# ADAPT_MAXREFDES117.net
KiCad netlist of a schematic drawn in EAGLE
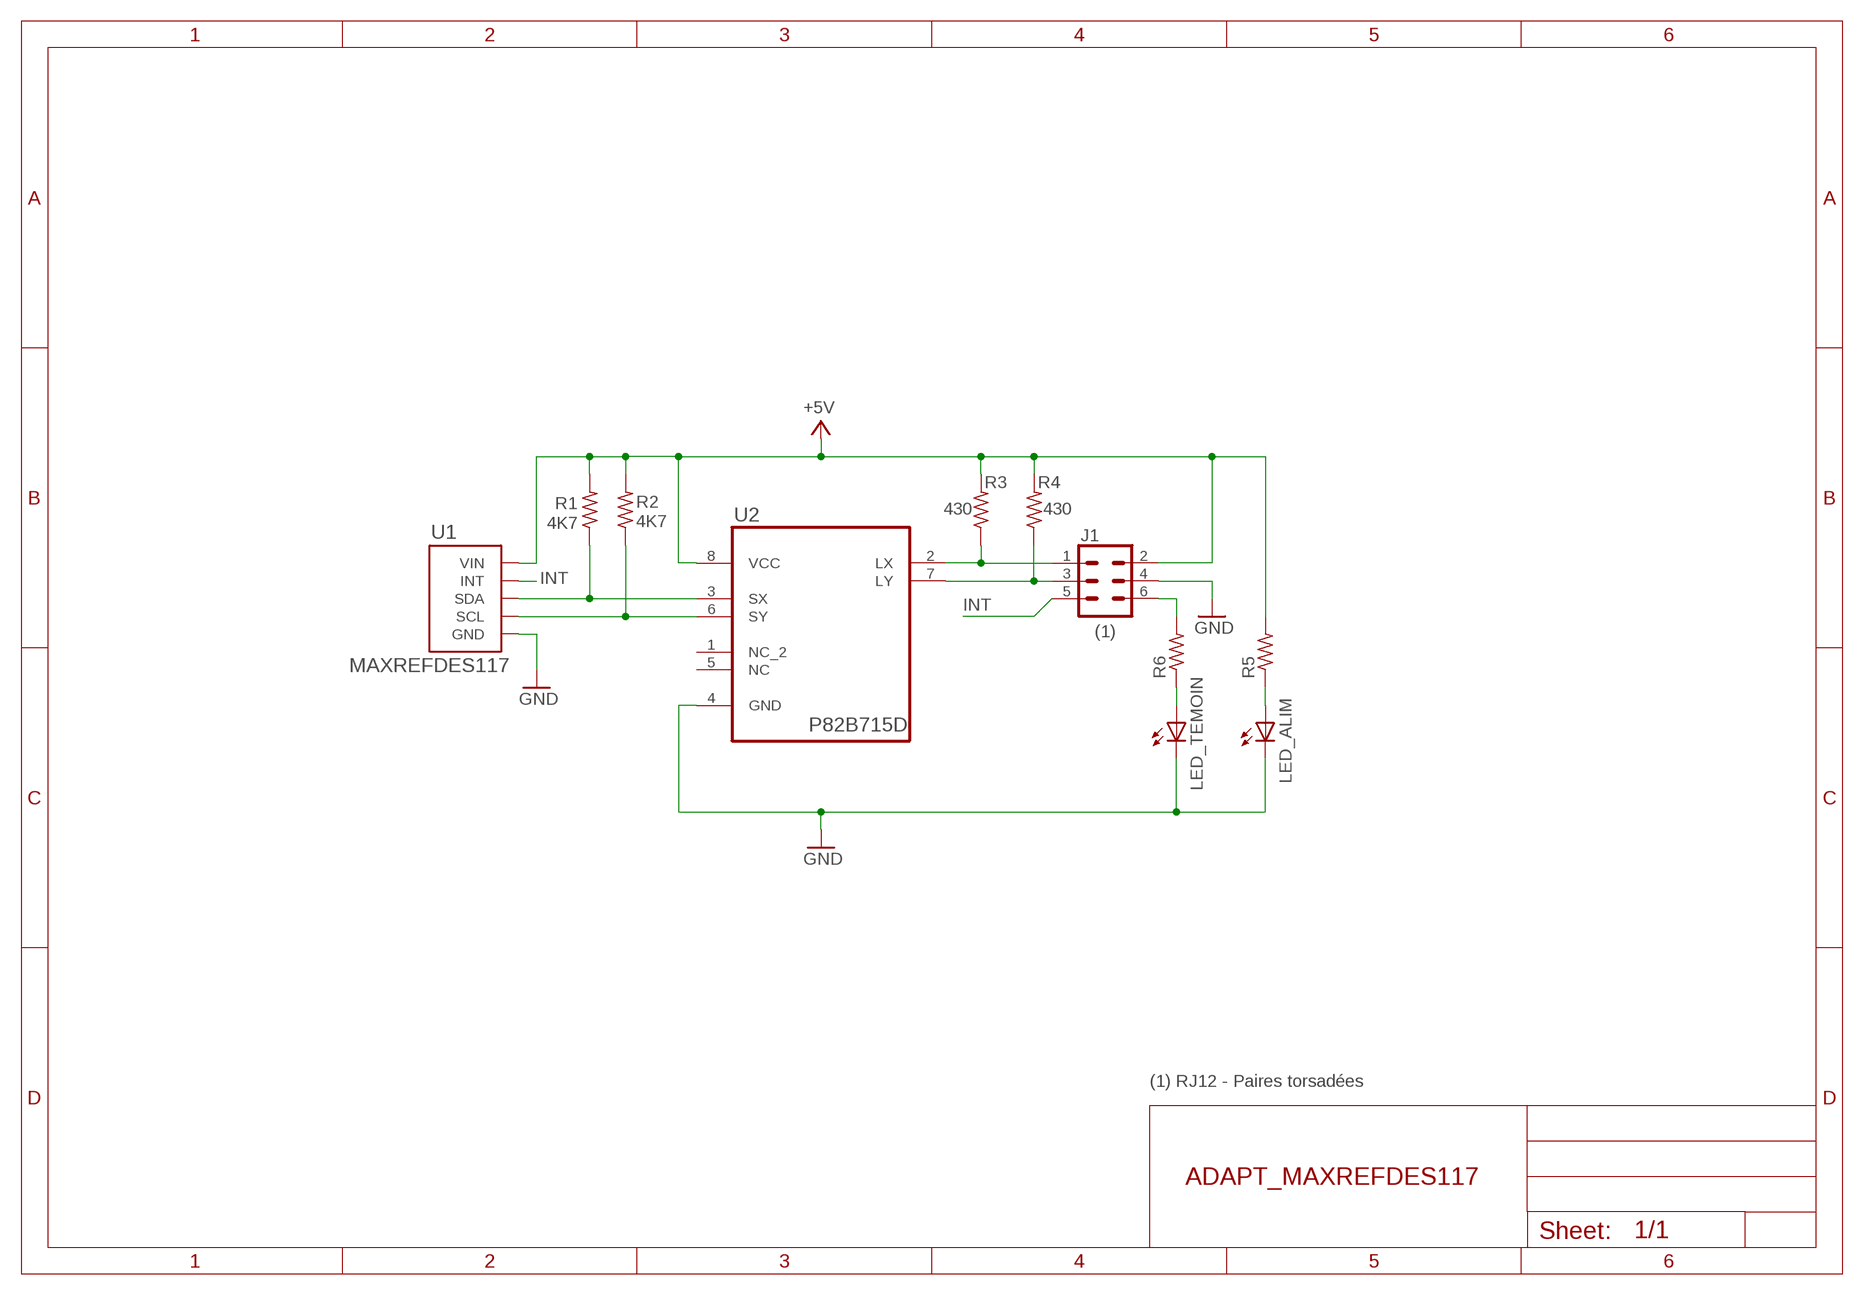
[diagram p0: schematic, sheet 1]

(export (version "E")
  (design (tool "Eeschema 10.0.6"))
  (components
    (comp (ref "J1")
      (value "CONN_03X2NO_SILK")
      (footprint "eagle-import:2X3-NS")
      (libsource (lib "eagle-import") (part "CONN_03X2NO_SILK"))
    )
    (comp (ref "LED_ALIM")
      (value "LEDFAB1206")
      (footprint "eagle-import:LED1206FAB")
      (libsource (lib "eagle-import") (part "LEDFAB1206"))
    )
    (comp (ref "LED_TEMOIN")
      (value "LEDFAB1206")
      (footprint "eagle-import:LED1206FAB")
      (libsource (lib "eagle-import") (part "LEDFAB1206"))
    )
    (comp (ref "R1")
      (value "4K7")
      (footprint "eagle-import:R1206FAB")
      (libsource (lib "eagle-import") (part "RES-US1206FAB"))
    )
    (comp (ref "R2")
      (value "4K7")
      (footprint "eagle-import:R1206FAB")
      (libsource (lib "eagle-import") (part "RES-US1206FAB"))
    )
    (comp (ref "R3")
      (value "430")
      (footprint "eagle-import:R1206FAB")
      (libsource (lib "eagle-import") (part "RES-US1206FAB"))
    )
    (comp (ref "R4")
      (value "430")
      (footprint "eagle-import:R1206FAB")
      (libsource (lib "eagle-import") (part "RES-US1206FAB"))
    )
    (comp (ref "R5")
      (value "RES-US1206FAB")
      (footprint "eagle-import:R1206FAB")
      (libsource (lib "eagle-import") (part "RES-US1206FAB"))
    )
    (comp (ref "R6")
      (value "RES-US1206FAB")
      (footprint "eagle-import:R1206FAB")
      (libsource (lib "eagle-import") (part "RES-US1206FAB"))
    )
    (comp (ref "U1")
      (value "MAXREFDES117")
      (footprint "eagle-import:MAXREFDES117")
      (libsource (lib "eagle-import") (part "MAXREFDES117"))
    )
    (comp (ref "U2")
      (value "P82B715D")
      (footprint "eagle-import:SOIC127P600X175-8N")
      (fields (field (name "MF") "Texas Instruments"))
      (libsource (lib "eagle-import") (part "P82B715D"))
    )
  )
  (nets
    (net (code "1") (name "+5V") (class "Default")
      (node (ref "J1") (pin "2") (pinfunction "2_2") (pintype "bidirectional"))
      (node (ref "R1") (pin "2") (pinfunction "2_2") (pintype "passive"))
      (node (ref "R2") (pin "2") (pinfunction "2_2") (pintype "passive"))
      (node (ref "R3") (pin "2") (pinfunction "2_2") (pintype "passive"))
      (node (ref "R4") (pin "2") (pinfunction "2_2") (pintype "passive"))
      (node (ref "R5") (pin "2") (pinfunction "2_2") (pintype "passive"))
      (node (ref "U1") (pin "VIN") (pinfunction "VIN_VIN") (pintype "bidirectional"))
      (node (ref "U2") (pin "8") (pinfunction "VCC_8") (pintype "power_in"))
    )
    (net (code "2") (name "/INT") (class "Default")
      (node (ref "J1") (pin "5") (pinfunction "5_5") (pintype "bidirectional"))
      (node (ref "U1") (pin "INT$1") (pinfunction "INT_INT$1") (pintype "bidirectional"))
      (node (ref "U1") (pin "INT$2") (pinfunction "INT_INT$2") (pintype "bidirectional"))
    )
    (net (code "3") (name "GND") (class "Default")
      (node (ref "J1") (pin "4") (pinfunction "4_4") (pintype "bidirectional"))
      (node (ref "LED_ALIM") (pin "2") (pinfunction "C_2") (pintype "passive"))
      (node (ref "LED_TEMOIN") (pin "2") (pinfunction "C_2") (pintype "passive"))
      (node (ref "U1") (pin "GND") (pinfunction "GND_GND") (pintype "bidirectional"))
      (node (ref "U2") (pin "4") (pinfunction "GND_4") (pintype "passive"))
    )
    (net (code "4") (name "Net-(J1-Pad6)") (class "Default")
      (node (ref "J1") (pin "6") (pinfunction "6_6") (pintype "bidirectional"))
      (node (ref "R6") (pin "2") (pinfunction "2_2") (pintype "passive"))
    )
    (net (code "5") (name "Net-(LED_ALIM-A)") (class "Default")
      (node (ref "LED_ALIM") (pin "1") (pinfunction "A_1") (pintype "passive"))
      (node (ref "R5") (pin "1") (pinfunction "1_1") (pintype "passive"))
    )
    (net (code "6") (name "Net-(LED_TEMOIN-A)") (class "Default")
      (node (ref "LED_TEMOIN") (pin "1") (pinfunction "A_1") (pintype "passive"))
      (node (ref "R6") (pin "1") (pinfunction "1_1") (pintype "passive"))
    )
    (net (code "7") (name "Net-(U2-LX)") (class "Default")
      (node (ref "J1") (pin "1") (pinfunction "1_1") (pintype "bidirectional"))
      (node (ref "R3") (pin "1") (pinfunction "1_1") (pintype "passive"))
      (node (ref "U2") (pin "2") (pinfunction "LX_2") (pintype "output"))
    )
    (net (code "8") (name "Net-(U2-LY)") (class "Default")
      (node (ref "J1") (pin "3") (pinfunction "3_3") (pintype "bidirectional"))
      (node (ref "R4") (pin "1") (pinfunction "1_1") (pintype "passive"))
      (node (ref "U2") (pin "7") (pinfunction "LY_7") (pintype "output"))
    )
    (net (code "9") (name "Net-(U2-SX)") (class "Default")
      (node (ref "R1") (pin "1") (pinfunction "1_1") (pintype "passive"))
      (node (ref "U1") (pin "SDA$1") (pinfunction "SDA_SDA$1") (pintype "bidirectional"))
      (node (ref "U1") (pin "SDA$2") (pinfunction "SDA_SDA$2") (pintype "bidirectional"))
      (node (ref "U2") (pin "3") (pinfunction "SX_3") (pintype "input"))
    )
    (net (code "10") (name "Net-(U2-SY)") (class "Default")
      (node (ref "R2") (pin "1") (pinfunction "1_1") (pintype "passive"))
      (node (ref "U1") (pin "SCL$1") (pinfunction "SCL_SCL$1") (pintype "bidirectional"))
      (node (ref "U1") (pin "SCL$2") (pinfunction "SCL_SCL$2") (pintype "bidirectional"))
      (node (ref "U2") (pin "6") (pinfunction "SY_6") (pintype "input"))
    )
    (net (code "11") (name "unconnected-(U2-NC-Pad5)") (class "Default")
      (node (ref "U2") (pin "5") (pinfunction "NC_5") (pintype "no_connect"))
    )
    (net (code "12") (name "unconnected-(U2-NC_2-Pad1)") (class "Default")
      (node (ref "U2") (pin "1") (pinfunction "NC_2_1") (pintype "no_connect"))
    )
  )
)
